# DIAGONAL_POLYPHONIC_SEQUENCER_SIMPLER_VE.net
KiCad netlist of a schematic drawn in EAGLE
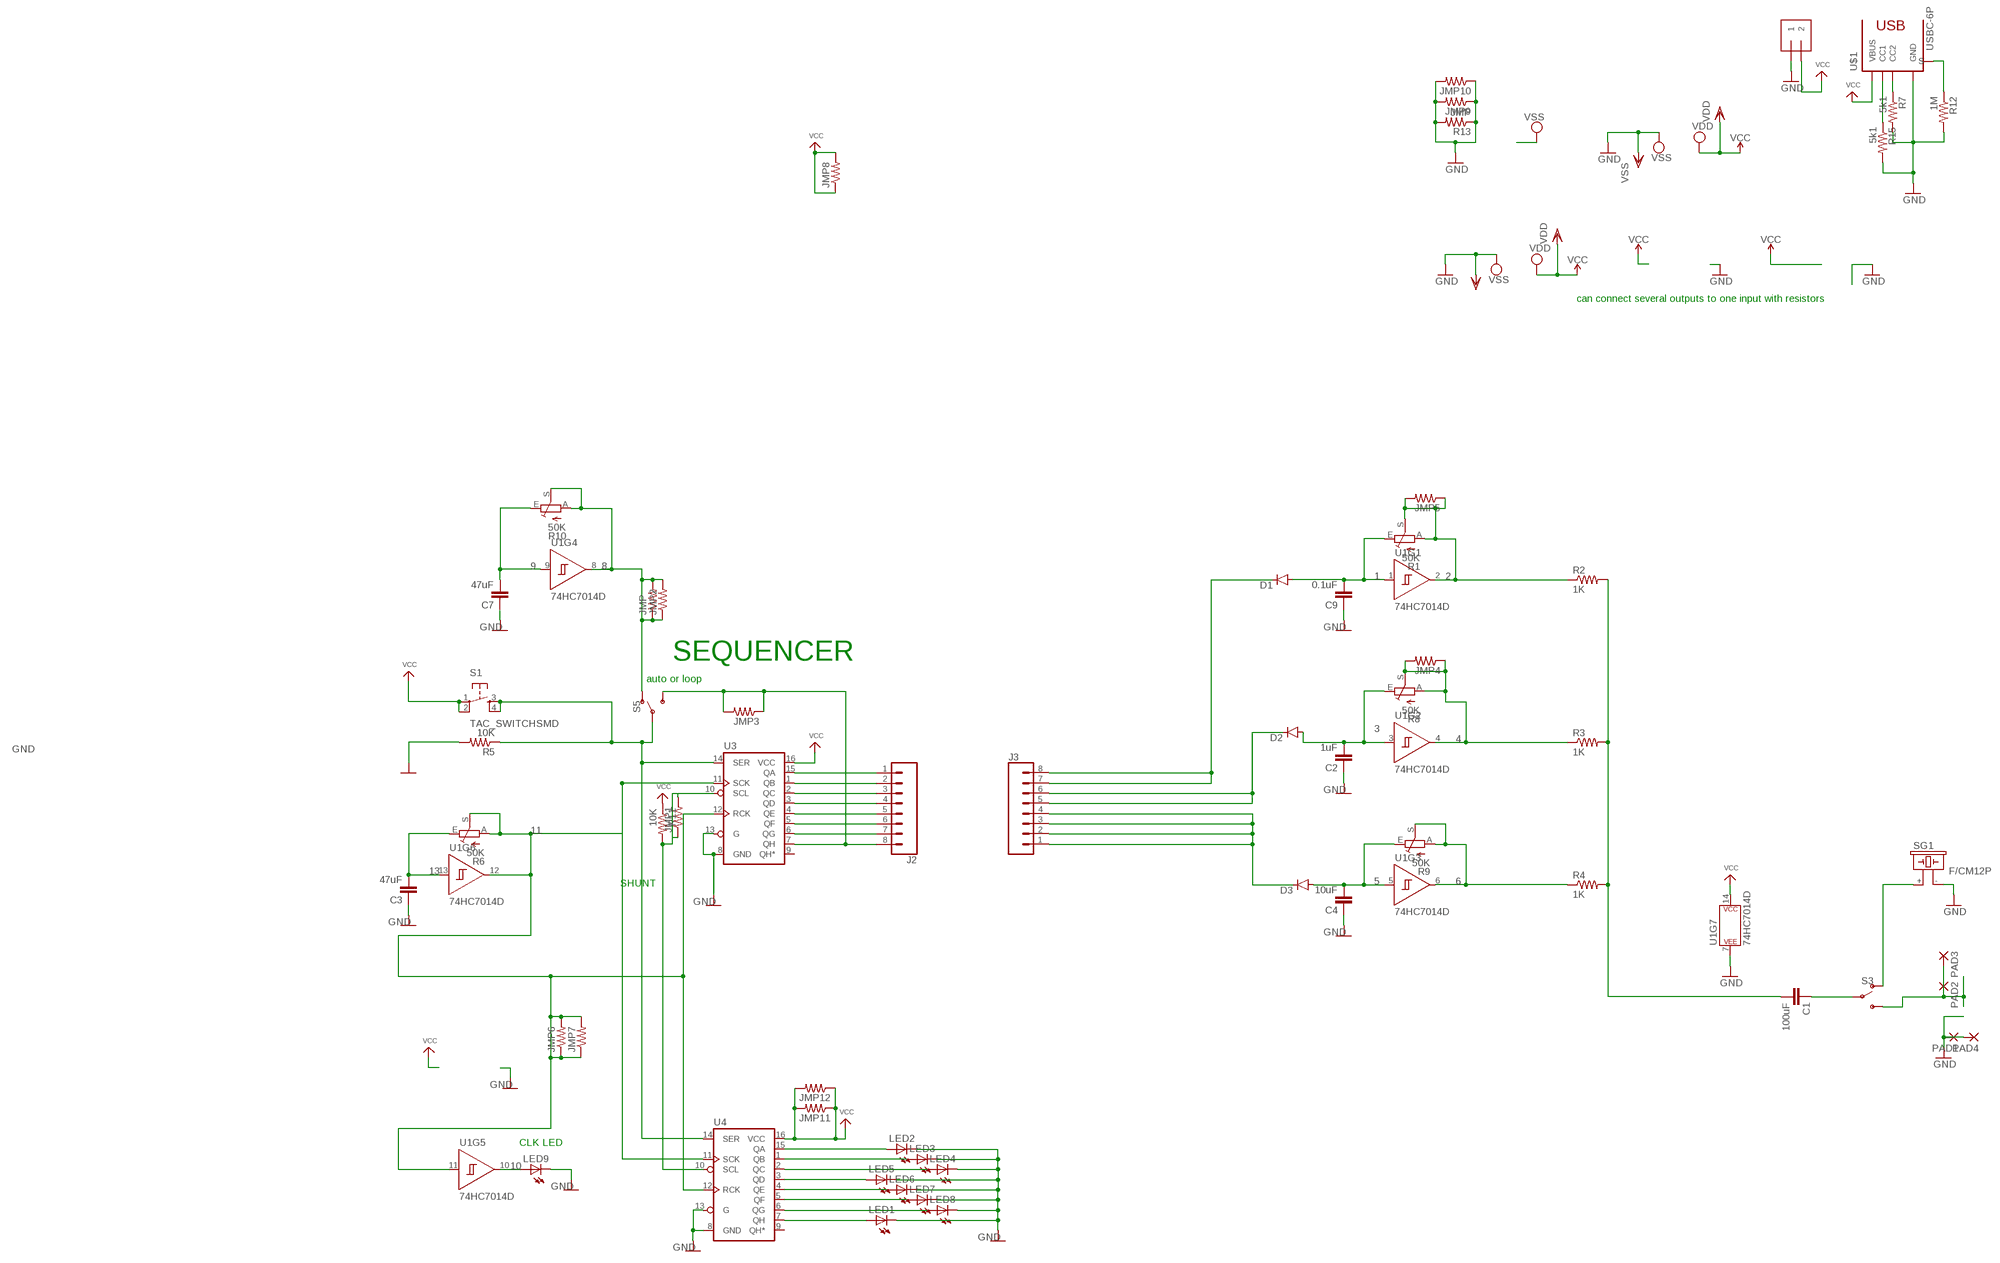
[diagram p0: schematic, sheet 1]

(export (version "E")
  (design (tool "Eeschema 10.0.6"))
  (components
    (comp (ref "C1")
      (value "100uF")
      (footprint "eagle-import:1206")
      (libsource (lib "eagle-import") (part "1.0UF-1206-50V-10%"))
    )
    (comp (ref "C2")
      (value "1uF")
      (footprint "eagle-import:1206")
      (libsource (lib "eagle-import") (part "1.0UF-1206-50V-10%"))
    )
    (comp (ref "C3")
      (value "47uF")
      (footprint "eagle-import:1206")
      (libsource (lib "eagle-import") (part "1.0UF-1206-50V-10%"))
    )
    (comp (ref "C4")
      (value "10uF")
      (footprint "eagle-import:1206")
      (libsource (lib "eagle-import") (part "1.0UF-1206-50V-10%"))
    )
    (comp (ref "C7")
      (value "47uF")
      (footprint "eagle-import:1206")
      (libsource (lib "eagle-import") (part "1.0UF-1206-50V-10%"))
    )
    (comp (ref "C9")
      (value "0.1uF")
      (footprint "eagle-import:1206")
      (libsource (lib "eagle-import") (part "1.0UF-1206-50V-10%"))
    )
    (comp (ref "D1")
      (value "DIODEDO214AA")
      (footprint "eagle-import:DO-214AA")
      (libsource (lib "eagle-import") (part "DIODEDO214AA"))
    )
    (comp (ref "D2")
      (value "DIODEDO214AA")
      (footprint "eagle-import:DO-214AA")
      (libsource (lib "eagle-import") (part "DIODEDO214AA"))
    )
    (comp (ref "D3")
      (value "DIODEDO214AA")
      (footprint "eagle-import:DO-214AA")
      (libsource (lib "eagle-import") (part "DIODEDO214AA"))
    )
    (comp (ref "J1")
      (value "1X2-3.5MM")
      (footprint "eagle-import:1X2-3.5MM")
      (libsource (lib "eagle-import") (part "1X2-3.5MM"))
    )
    (comp (ref "J2")
      (value "CONN_08SMD-STRAIGHT-ALT-FEMALE")
      (footprint "eagle-import:1X08_SMD_ALT")
      (libsource (lib "eagle-import") (part "CONN_08SMD-STRAIGHT-ALT-FEMALE"))
    )
    (comp (ref "J3")
      (value "CONN_08SMD-STRAIGHT-ALT-FEMALE")
      (footprint "eagle-import:1X08_SMD_ALT")
      (libsource (lib "eagle-import") (part "CONN_08SMD-STRAIGHT-ALT-FEMALE"))
    )
    (comp (ref "JMP")
      (value "R-US_R1206")
      (footprint "eagle-import:R1206")
      (libsource (lib "eagle-import") (part "R-US_R1206"))
    )
    (comp (ref "JMP1")
      (value "R-US_R1206")
      (footprint "eagle-import:R1206")
      (libsource (lib "eagle-import") (part "R-US_R1206"))
    )
    (comp (ref "JMP2")
      (value "R-US_R1206")
      (footprint "eagle-import:R1206")
      (libsource (lib "eagle-import") (part "R-US_R1206"))
    )
    (comp (ref "JMP3")
      (value "R-US_R1206")
      (footprint "eagle-import:R1206")
      (libsource (lib "eagle-import") (part "R-US_R1206"))
    )
    (comp (ref "JMP4")
      (value "R-US_R1206")
      (footprint "eagle-import:R1206")
      (libsource (lib "eagle-import") (part "R-US_R1206"))
    )
    (comp (ref "JMP5")
      (value "R-US_R1206")
      (footprint "eagle-import:R1206")
      (libsource (lib "eagle-import") (part "R-US_R1206"))
    )
    (comp (ref "JMP6")
      (value "R-US_R1206")
      (footprint "eagle-import:R1206")
      (libsource (lib "eagle-import") (part "R-US_R1206"))
    )
    (comp (ref "JMP7")
      (value "R-US_R1206")
      (footprint "eagle-import:R1206")
      (libsource (lib "eagle-import") (part "R-US_R1206"))
    )
    (comp (ref "JMP8")
      (value "R-US_R1206")
      (footprint "eagle-import:R1206")
      (libsource (lib "eagle-import") (part "R-US_R1206"))
    )
    (comp (ref "JMP9")
      (value "R-US_R1206")
      (footprint "eagle-import:R1206")
      (libsource (lib "eagle-import") (part "R-US_R1206"))
    )
    (comp (ref "JMP10")
      (value "R-US_R1206")
      (footprint "eagle-import:R1206")
      (libsource (lib "eagle-import") (part "R-US_R1206"))
    )
    (comp (ref "JMP11")
      (value "R-US_R1206")
      (footprint "eagle-import:R1206")
      (libsource (lib "eagle-import") (part "R-US_R1206"))
    )
    (comp (ref "JMP12")
      (value "R-US_R1206")
      (footprint "eagle-import:R1206")
      (libsource (lib "eagle-import") (part "R-US_R1206"))
    )
    (comp (ref "LED1")
      (value "LEDCHIPLED_1206")
      (footprint "eagle-import:CHIPLED_1206")
      (libsource (lib "eagle-import") (part "LEDCHIPLED_1206"))
    )
    (comp (ref "LED2")
      (value "LEDCHIPLED_1206")
      (footprint "eagle-import:CHIPLED_1206")
      (libsource (lib "eagle-import") (part "LEDCHIPLED_1206"))
    )
    (comp (ref "LED3")
      (value "LEDCHIPLED_1206")
      (footprint "eagle-import:CHIPLED_1206")
      (libsource (lib "eagle-import") (part "LEDCHIPLED_1206"))
    )
    (comp (ref "LED4")
      (value "LEDCHIPLED_1206")
      (footprint "eagle-import:CHIPLED_1206")
      (libsource (lib "eagle-import") (part "LEDCHIPLED_1206"))
    )
    (comp (ref "LED5")
      (value "LEDCHIPLED_1206")
      (footprint "eagle-import:CHIPLED_1206")
      (libsource (lib "eagle-import") (part "LEDCHIPLED_1206"))
    )
    (comp (ref "LED6")
      (value "LEDCHIPLED_1206")
      (footprint "eagle-import:CHIPLED_1206")
      (libsource (lib "eagle-import") (part "LEDCHIPLED_1206"))
    )
    (comp (ref "LED7")
      (value "LEDCHIPLED_1206")
      (footprint "eagle-import:CHIPLED_1206")
      (libsource (lib "eagle-import") (part "LEDCHIPLED_1206"))
    )
    (comp (ref "LED8")
      (value "LEDCHIPLED_1206")
      (footprint "eagle-import:CHIPLED_1206")
      (libsource (lib "eagle-import") (part "LEDCHIPLED_1206"))
    )
    (comp (ref "LED9")
      (value "LEDCHIPLED_1206")
      (footprint "eagle-import:CHIPLED_1206")
      (libsource (lib "eagle-import") (part "LEDCHIPLED_1206"))
    )
    (comp (ref "PAD1")
      (value "SMD5")
      (footprint "eagle-import:SMD2,54-5,08")
      (libsource (lib "eagle-import") (part "SMD5"))
    )
    (comp (ref "PAD2")
      (value "SMD5")
      (footprint "eagle-import:SMD2,54-5,08")
      (libsource (lib "eagle-import") (part "SMD5"))
    )
    (comp (ref "PAD3")
      (value "SMD5")
      (footprint "eagle-import:SMD2,54-5,08")
      (libsource (lib "eagle-import") (part "SMD5"))
    )
    (comp (ref "PAD4")
      (value "SMD5")
      (footprint "eagle-import:SMD2,54-5,08")
      (libsource (lib "eagle-import") (part "SMD5"))
    )
    (comp (ref "R1")
      (value "50K")
      (footprint "eagle-import:CA9V")
      (libsource (lib "eagle-import") (part "TRIM_EU-CA9V"))
    )
    (comp (ref "R2")
      (value "1K")
      (footprint "eagle-import:R1206")
      (libsource (lib "eagle-import") (part "R-US_R1206"))
    )
    (comp (ref "R3")
      (value "1K")
      (footprint "eagle-import:R1206")
      (libsource (lib "eagle-import") (part "R-US_R1206"))
    )
    (comp (ref "R4")
      (value "1K")
      (footprint "eagle-import:R1206")
      (libsource (lib "eagle-import") (part "R-US_R1206"))
    )
    (comp (ref "R5")
      (value "10K")
      (footprint "eagle-import:R1206")
      (libsource (lib "eagle-import") (part "R-US_R1206"))
    )
    (comp (ref "R6")
      (value "50K")
      (footprint "eagle-import:CA9V")
      (libsource (lib "eagle-import") (part "TRIM_EU-CA9V"))
    )
    (comp (ref "R7")
      (value "5k1")
      (footprint "eagle-import:R1206")
      (libsource (lib "eagle-import") (part "R-US_R1206"))
    )
    (comp (ref "R8")
      (value "50K")
      (footprint "eagle-import:CA9V")
      (libsource (lib "eagle-import") (part "TRIM_EU-CA9V"))
    )
    (comp (ref "R9")
      (value "50K")
      (footprint "eagle-import:CA9V")
      (libsource (lib "eagle-import") (part "TRIM_EU-CA9V"))
    )
    (comp (ref "R10")
      (value "50K")
      (footprint "eagle-import:CA9V")
      (libsource (lib "eagle-import") (part "TRIM_EU-CA9V"))
    )
    (comp (ref "R11")
      (value "10K")
      (footprint "eagle-import:R1206")
      (libsource (lib "eagle-import") (part "R-US_R1206"))
    )
    (comp (ref "R12")
      (value "1M")
      (footprint "eagle-import:R1206")
      (libsource (lib "eagle-import") (part "R-US_R1206"))
    )
    (comp (ref "R13")
      (value "JMP")
      (footprint "eagle-import:R1206")
      (libsource (lib "eagle-import") (part "R-US_R1206"))
    )
    (comp (ref "R15")
      (value "5k1")
      (footprint "eagle-import:R1206")
      (libsource (lib "eagle-import") (part "R-US_R1206"))
    )
    (comp (ref "S1")
      (value "TAC_SWITCHSMD")
      (footprint "eagle-import:TACTILE-SWITCH-SMD")
      (libsource (lib "eagle-import") (part "TAC_SWITCHSMD"))
    )
    (comp (ref "S3")
      (value "SWITCH-SPDT-SMD-AYZ0202")
      (footprint "eagle-import:SWITCH_DPDT_SMD_AYZ0202")
      (libsource (lib "eagle-import") (part "SWITCH-SPDT-SMD-AYZ0202"))
    )
    (comp (ref "S5")
      (value "SWITCH-SPDT-SMD-AYZ0202")
      (footprint "eagle-import:SWITCH_DPDT_SMD_AYZ0202")
      (libsource (lib "eagle-import") (part "SWITCH-SPDT-SMD-AYZ0202"))
    )
    (comp (ref "SG1")
      (value "F/CM12P")
      (footprint "eagle-import:F_CM12P")
      (libsource (lib "eagle-import") (part "F/CM12P"))
    )
    (comp (ref "U$1")
      (value "USBC-6P")
      (footprint "eagle-import:USCX-06FX-XXMX-01")
      (libsource (lib "eagle-import") (part "USBC-6P"))
    )
    (comp (ref "U1")
      (value "74HC7014D")
      (footprint "eagle-import:SO14")
      (libsource (lib "eagle-import") (part "747014DHC"))
    )
    (comp (ref "U3")
      (value "74595")
      (footprint "eagle-import:TSSOP16")
      (libsource (lib "eagle-import") (part "74595"))
    )
    (comp (ref "U4")
      (value "74595")
      (footprint "eagle-import:TSSOP16")
      (libsource (lib "eagle-import") (part "74595"))
    )
  )
  (nets
    (net (code "1") (name "/1") (class "Default")
      (node (ref "C9") (pin "2") (pinfunction "2_2") (pintype "passive"))
      (node (ref "D1") (pin "A") (pinfunction "A_A") (pintype "passive"))
      (node (ref "R1") (pin "E") (pinfunction "E_E") (pintype "passive"))
      (node (ref "U1") (pin "1") (pinfunction "A_1") (pintype "bidirectional"))
    )
    (net (code "2") (name "/2") (class "Default")
      (node (ref "JMP5") (pin "1") (pinfunction "1_1") (pintype "passive"))
      (node (ref "JMP5") (pin "2") (pinfunction "2_2") (pintype "passive"))
      (node (ref "R1") (pin "A") (pinfunction "A_A") (pintype "passive"))
      (node (ref "R1") (pin "S") (pinfunction "S_S") (pintype "passive"))
      (node (ref "R2") (pin "1") (pinfunction "1_1") (pintype "passive"))
      (node (ref "U1") (pin "2") (pinfunction "Y_2") (pintype "bidirectional"))
    )
    (net (code "3") (name "/3") (class "Default")
      (node (ref "C2") (pin "2") (pinfunction "2_2") (pintype "passive"))
      (node (ref "D2") (pin "A") (pinfunction "A_A") (pintype "passive"))
      (node (ref "R8") (pin "E") (pinfunction "E_E") (pintype "passive"))
      (node (ref "U1") (pin "3") (pinfunction "A_3") (pintype "bidirectional"))
    )
    (net (code "4") (name "/4") (class "Default")
      (node (ref "JMP4") (pin "1") (pinfunction "1_1") (pintype "passive"))
      (node (ref "JMP4") (pin "2") (pinfunction "2_2") (pintype "passive"))
      (node (ref "R3") (pin "1") (pinfunction "1_1") (pintype "passive"))
      (node (ref "R8") (pin "A") (pinfunction "A_A") (pintype "passive"))
      (node (ref "R8") (pin "S") (pinfunction "S_S") (pintype "passive"))
      (node (ref "U1") (pin "4") (pinfunction "Y_4") (pintype "bidirectional"))
    )
    (net (code "5") (name "/5") (class "Default")
      (node (ref "C4") (pin "2") (pinfunction "2_2") (pintype "passive"))
      (node (ref "D3") (pin "A") (pinfunction "A_A") (pintype "passive"))
      (node (ref "R9") (pin "E") (pinfunction "E_E") (pintype "passive"))
      (node (ref "U1") (pin "5") (pinfunction "A_5") (pintype "bidirectional"))
    )
    (net (code "6") (name "/6") (class "Default")
      (node (ref "R4") (pin "1") (pinfunction "1_1") (pintype "passive"))
      (node (ref "R9") (pin "A") (pinfunction "A_A") (pintype "passive"))
      (node (ref "R9") (pin "S") (pinfunction "S_S") (pintype "passive"))
      (node (ref "U1") (pin "6") (pinfunction "Y_6") (pintype "bidirectional"))
    )
    (net (code "7") (name "/8") (class "Default")
      (node (ref "JMP") (pin "1") (pinfunction "1_1") (pintype "passive"))
      (node (ref "JMP") (pin "2") (pinfunction "2_2") (pintype "passive"))
      (node (ref "JMP2") (pin "1") (pinfunction "1_1") (pintype "passive"))
      (node (ref "JMP2") (pin "2") (pinfunction "2_2") (pintype "passive"))
      (node (ref "R10") (pin "A") (pinfunction "A_A") (pintype "passive"))
      (node (ref "R10") (pin "S") (pinfunction "S_S") (pintype "passive"))
      (node (ref "S5") (pin "1") (pinfunction "O_1") (pintype "passive"))
      (node (ref "U1") (pin "8") (pinfunction "Y_8") (pintype "bidirectional"))
    )
    (net (code "8") (name "/9") (class "Default")
      (node (ref "C7") (pin "2") (pinfunction "2_2") (pintype "passive"))
      (node (ref "R10") (pin "E") (pinfunction "E_E") (pintype "passive"))
      (node (ref "U1") (pin "9") (pinfunction "A_9") (pintype "bidirectional"))
    )
    (net (code "9") (name "/10") (class "Default")
      (node (ref "LED9") (pin "A") (pinfunction "A_A") (pintype "passive"))
      (node (ref "U1") (pin "10") (pinfunction "Y_10") (pintype "bidirectional"))
    )
    (net (code "10") (name "/11") (class "Default")
      (node (ref "JMP6") (pin "1") (pinfunction "1_1") (pintype "passive"))
      (node (ref "JMP6") (pin "2") (pinfunction "2_2") (pintype "passive"))
      (node (ref "JMP7") (pin "1") (pinfunction "1_1") (pintype "passive"))
      (node (ref "JMP7") (pin "2") (pinfunction "2_2") (pintype "passive"))
      (node (ref "R6") (pin "A") (pinfunction "A_A") (pintype "passive"))
      (node (ref "R6") (pin "S") (pinfunction "S_S") (pintype "passive"))
      (node (ref "U1") (pin "11") (pinfunction "A_11") (pintype "bidirectional"))
      (node (ref "U1") (pin "12") (pinfunction "Y_12") (pintype "bidirectional"))
      (node (ref "U3") (pin "11") (pinfunction "SCK_11") (pintype "input"))
      (node (ref "U3") (pin "12") (pinfunction "RCK_12") (pintype "input"))
      (node (ref "U4") (pin "11") (pinfunction "SCK_11") (pintype "input"))
      (node (ref "U4") (pin "12") (pinfunction "RCK_12") (pintype "input"))
    )
    (net (code "11") (name "/13") (class "Default")
      (node (ref "C3") (pin "2") (pinfunction "2_2") (pintype "passive"))
      (node (ref "R6") (pin "E") (pinfunction "E_E") (pintype "passive"))
      (node (ref "U1") (pin "13") (pinfunction "A_13") (pintype "bidirectional"))
    )
    (net (code "12") (name "GND") (class "Default")
      (node (ref "C2") (pin "1") (pinfunction "1_1") (pintype "passive"))
      (node (ref "C3") (pin "1") (pinfunction "1_1") (pintype "passive"))
      (node (ref "C4") (pin "1") (pinfunction "1_1") (pintype "passive"))
      (node (ref "C7") (pin "1") (pinfunction "1_1") (pintype "passive"))
      (node (ref "C9") (pin "1") (pinfunction "1_1") (pintype "passive"))
      (node (ref "J1") (pin "1") (pinfunction "1_1") (pintype "passive"))
      (node (ref "JMP10") (pin "1") (pinfunction "1_1") (pintype "passive"))
      (node (ref "JMP10") (pin "2") (pinfunction "2_2") (pintype "passive"))
      (node (ref "JMP9") (pin "1") (pinfunction "1_1") (pintype "passive"))
      (node (ref "JMP9") (pin "2") (pinfunction "2_2") (pintype "passive"))
      (node (ref "LED1") (pin "C") (pinfunction "C_C") (pintype "passive"))
      (node (ref "LED2") (pin "C") (pinfunction "C_C") (pintype "passive"))
      (node (ref "LED3") (pin "C") (pinfunction "C_C") (pintype "passive"))
      (node (ref "LED4") (pin "C") (pinfunction "C_C") (pintype "passive"))
      (node (ref "LED5") (pin "C") (pinfunction "C_C") (pintype "passive"))
      (node (ref "LED6") (pin "C") (pinfunction "C_C") (pintype "passive"))
      (node (ref "LED7") (pin "C") (pinfunction "C_C") (pintype "passive"))
      (node (ref "LED8") (pin "C") (pinfunction "C_C") (pintype "passive"))
      (node (ref "LED9") (pin "C") (pinfunction "C_C") (pintype "passive"))
      (node (ref "PAD1") (pin "1") (pinfunction "P_1") (pintype "passive"))
      (node (ref "PAD4") (pin "1") (pinfunction "P_1") (pintype "passive"))
      (node (ref "R12") (pin "2") (pinfunction "2_2") (pintype "passive"))
      (node (ref "R13") (pin "1") (pinfunction "1_1") (pintype "passive"))
      (node (ref "R13") (pin "2") (pinfunction "2_2") (pintype "passive"))
      (node (ref "R15") (pin "2") (pinfunction "2_2") (pintype "passive"))
      (node (ref "R5") (pin "2") (pinfunction "2_2") (pintype "passive"))
      (node (ref "R7") (pin "2") (pinfunction "2_2") (pintype "passive"))
      (node (ref "SG1") (pin "-") (pinfunction "2_-") (pintype "passive"))
      (node (ref "U$1") (pin "GND1") (pinfunction "GND_GND1") (pintype "power_in"))
      (node (ref "U$1") (pin "GND2") (pinfunction "GND_GND2") (pintype "power_in"))
      (node (ref "U1") (pin "7") (pinfunction "P$V-_7") (pintype "bidirectional"))
      (node (ref "U3") (pin "13") (pinfunction "G_13") (pintype "input"))
      (node (ref "U3") (pin "8") (pinfunction "GND_8") (pintype "power_in"))
      (node (ref "U4") (pin "13") (pinfunction "G_13") (pintype "input"))
      (node (ref "U4") (pin "8") (pinfunction "GND_8") (pintype "power_in"))
    )
    (net (code "13") (name "Net-(C1-Pad2)") (class "Default")
      (node (ref "C1") (pin "2") (pinfunction "2_2") (pintype "passive"))
      (node (ref "R2") (pin "2") (pinfunction "2_2") (pintype "passive"))
      (node (ref "R3") (pin "2") (pinfunction "2_2") (pintype "passive"))
      (node (ref "R4") (pin "2") (pinfunction "2_2") (pintype "passive"))
    )
    (net (code "14") (name "Net-(D1-PadC)") (class "Default")
      (node (ref "D1") (pin "C") (pinfunction "C_C") (pintype "passive"))
      (node (ref "J3") (pin "7") (pinfunction "7_7") (pintype "passive"))
      (node (ref "J3") (pin "8") (pinfunction "8_8") (pintype "passive"))
    )
    (net (code "15") (name "Net-(D2-PadC)") (class "Default")
      (node (ref "D2") (pin "C") (pinfunction "C_C") (pintype "passive"))
      (node (ref "J3") (pin "5") (pinfunction "5_5") (pintype "passive"))
      (node (ref "J3") (pin "6") (pinfunction "6_6") (pintype "passive"))
    )
    (net (code "16") (name "Net-(D3-PadC)") (class "Default")
      (node (ref "D3") (pin "C") (pinfunction "C_C") (pintype "passive"))
      (node (ref "J3") (pin "1") (pinfunction "1_1") (pintype "passive"))
      (node (ref "J3") (pin "2") (pinfunction "2_2") (pintype "passive"))
      (node (ref "J3") (pin "3") (pinfunction "3_3") (pintype "passive"))
      (node (ref "J3") (pin "4") (pinfunction "4_4") (pintype "passive"))
    )
    (net (code "17") (name "Net-(PAD2-P)") (class "Default")
      (node (ref "PAD2") (pin "1") (pinfunction "P_1") (pintype "passive"))
      (node (ref "PAD3") (pin "1") (pinfunction "P_1") (pintype "passive"))
      (node (ref "S3") (pin "3") (pinfunction "S_3") (pintype "passive"))
    )
    (net (code "18") (name "Net-(R7-Pad1)") (class "Default")
      (node (ref "R7") (pin "1") (pinfunction "1_1") (pintype "passive"))
      (node (ref "U$1") (pin "CC2") (pinfunction "CC2_CC2") (pintype "bidirectional"))
    )
    (net (code "19") (name "Net-(R12-Pad1)") (class "Default")
      (node (ref "R12") (pin "1") (pinfunction "1_1") (pintype "passive"))
      (node (ref "U$1") (pin "SHIELD1") (pinfunction "S_SHIELD1") (pintype "passive"))
      (node (ref "U$1") (pin "SHIELD2") (pinfunction "S_SHIELD2") (pintype "passive"))
      (node (ref "U$1") (pin "SHIELD3") (pinfunction "S_SHIELD3") (pintype "passive"))
      (node (ref "U$1") (pin "SHIELD4") (pinfunction "S_SHIELD4") (pintype "passive"))
    )
    (net (code "20") (name "Net-(R15-Pad1)") (class "Default")
      (node (ref "R15") (pin "1") (pinfunction "1_1") (pintype "passive"))
      (node (ref "U$1") (pin "CC1") (pinfunction "CC1_CC1") (pintype "bidirectional"))
    )
    (net (code "21") (name "Net-(S3-O)") (class "Default")
      (node (ref "S3") (pin "1") (pinfunction "O_1") (pintype "passive"))
      (node (ref "SG1") (pin "+") (pinfunction "1_+") (pintype "passive"))
    )
    (net (code "22") (name "Net-(S3-P)") (class "Default")
      (node (ref "C1") (pin "1") (pinfunction "1_1") (pintype "passive"))
      (node (ref "S3") (pin "2") (pinfunction "P_2") (pintype "passive"))
    )
    (net (code "23") (name "Net-(S5-P)") (class "Default")
      (node (ref "R5") (pin "1") (pinfunction "1_1") (pintype "passive"))
      (node (ref "S1") (pin "3") (pinfunction "3_3") (pintype "passive"))
      (node (ref "S1") (pin "4") (pinfunction "4_4") (pintype "passive"))
      (node (ref "S5") (pin "2") (pinfunction "P_2") (pintype "passive"))
      (node (ref "U3") (pin "14") (pinfunction "SER_14") (pintype "input"))
      (node (ref "U4") (pin "14") (pinfunction "SER_14") (pintype "input"))
    )
    (net (code "24") (name "Net-(S5-S)") (class "Default")
      (node (ref "J2") (pin "8") (pinfunction "8_8") (pintype "passive"))
      (node (ref "JMP3") (pin "1") (pinfunction "1_1") (pintype "passive"))
      (node (ref "JMP3") (pin "2") (pinfunction "2_2") (pintype "passive"))
      (node (ref "S5") (pin "3") (pinfunction "S_3") (pintype "passive"))
      (node (ref "U3") (pin "7") (pinfunction "QH_7") (pintype "tri_state"))
    )
    (net (code "25") (name "Net-(U3-QA)") (class "Default")
      (node (ref "J2") (pin "1") (pinfunction "1_1") (pintype "passive"))
      (node (ref "U3") (pin "15") (pinfunction "QA_15") (pintype "tri_state"))
    )
    (net (code "26") (name "Net-(U3-QB)") (class "Default")
      (node (ref "J2") (pin "2") (pinfunction "2_2") (pintype "passive"))
      (node (ref "U3") (pin "1") (pinfunction "QB_1") (pintype "tri_state"))
    )
    (net (code "27") (name "Net-(U3-QC)") (class "Default")
      (node (ref "J2") (pin "3") (pinfunction "3_3") (pintype "passive"))
      (node (ref "U3") (pin "2") (pinfunction "QC_2") (pintype "tri_state"))
    )
    (net (code "28") (name "Net-(U3-QD)") (class "Default")
      (node (ref "J2") (pin "4") (pinfunction "4_4") (pintype "passive"))
      (node (ref "U3") (pin "3") (pinfunction "QD_3") (pintype "tri_state"))
    )
    (net (code "29") (name "Net-(U3-QE)") (class "Default")
      (node (ref "J2") (pin "5") (pinfunction "5_5") (pintype "passive"))
      (node (ref "U3") (pin "4") (pinfunction "QE_4") (pintype "tri_state"))
    )
    (net (code "30") (name "Net-(U3-QF)") (class "Default")
      (node (ref "J2") (pin "6") (pinfunction "6_6") (pintype "passive"))
      (node (ref "U3") (pin "5") (pinfunction "QF_5") (pintype "tri_state"))
    )
    (net (code "31") (name "Net-(U3-QG)") (class "Default")
      (node (ref "J2") (pin "7") (pinfunction "7_7") (pintype "passive"))
      (node (ref "U3") (pin "6") (pinfunction "QG_6") (pintype "tri_state"))
    )
    (net (code "32") (name "Net-(U3-SCL)") (class "Default")
      (node (ref "JMP1") (pin "1") (pinfunction "1_1") (pintype "passive"))
      (node (ref "JMP1") (pin "2") (pinfunction "2_2") (pintype "passive"))
      (node (ref "R11") (pin "2") (pinfunction "2_2") (pintype "passive"))
      (node (ref "U3") (pin "10") (pinfunction "SCL_10") (pintype "input"))
      (node (ref "U4") (pin "10") (pinfunction "SCL_10") (pintype "input"))
    )
    (net (code "33") (name "Net-(U4-QA)") (class "Default")
      (node (ref "LED2") (pin "A") (pinfunction "A_A") (pintype "passive"))
      (node (ref "U4") (pin "15") (pinfunction "QA_15") (pintype "tri_state"))
    )
    (net (code "34") (name "Net-(U4-QB)") (class "Default")
      (node (ref "LED3") (pin "A") (pinfunction "A_A") (pintype "passive"))
      (node (ref "U4") (pin "1") (pinfunction "QB_1") (pintype "tri_state"))
    )
    (net (code "35") (name "Net-(U4-QC)") (class "Default")
      (node (ref "LED4") (pin "A") (pinfunction "A_A") (pintype "passive"))
      (node (ref "U4") (pin "2") (pinfunction "QC_2") (pintype "tri_state"))
    )
    (net (code "36") (name "Net-(U4-QD)") (class "Default")
      (node (ref "LED5") (pin "A") (pinfunction "A_A") (pintype "passive"))
      (node (ref "U4") (pin "3") (pinfunction "QD_3") (pintype "tri_state"))
    )
    (net (code "37") (name "Net-(U4-QE)") (class "Default")
      (node (ref "LED6") (pin "A") (pinfunction "A_A") (pintype "passive"))
      (node (ref "U4") (pin "4") (pinfunction "QE_4") (pintype "tri_state"))
    )
    (net (code "38") (name "Net-(U4-QF)") (class "Default")
      (node (ref "LED7") (pin "A") (pinfunction "A_A") (pintype "passive"))
      (node (ref "U4") (pin "5") (pinfunction "QF_5") (pintype "tri_state"))
    )
    (net (code "39") (name "Net-(U4-QG)") (class "Default")
      (node (ref "LED8") (pin "A") (pinfunction "A_A") (pintype "passive"))
      (node (ref "U4") (pin "6") (pinfunction "QG_6") (pintype "tri_state"))
    )
    (net (code "40") (name "Net-(U4-QH)") (class "Default")
      (node (ref "LED1") (pin "A") (pinfunction "A_A") (pintype "passive"))
      (node (ref "U4") (pin "7") (pinfunction "QH_7") (pintype "tri_state"))
    )
    (net (code "41") (name "VCC") (class "Default")
      (node (ref "J1") (pin "2") (pinfunction "2_2") (pintype "passive"))
      (node (ref "JMP11") (pin "1") (pinfunction "1_1") (pintype "passive"))
      (node (ref "JMP11") (pin "2") (pinfunction "2_2") (pintype "passive"))
      (node (ref "JMP12") (pin "1") (pinfunction "1_1") (pintype "passive"))
      (node (ref "JMP12") (pin "2") (pinfunction "2_2") (pintype "passive"))
      (node (ref "JMP8") (pin "1") (pinfunction "1_1") (pintype "passive"))
      (node (ref "JMP8") (pin "2") (pinfunction "2_2") (pintype "passive"))
      (node (ref "R11") (pin "1") (pinfunction "1_1") (pintype "passive"))
      (node (ref "S1") (pin "1") (pinfunction "1_1") (pintype "passive"))
      (node (ref "S1") (pin "2") (pinfunction "2_2") (pintype "passive"))
      (node (ref "U$1") (pin "VBUS1") (pinfunction "VBUS_VBUS1") (pintype "power_in"))
      (node (ref "U$1") (pin "VBUS2") (pinfunction "VBUS_VBUS2") (pintype "power_in"))
      (node (ref "U1") (pin "14") (pinfunction "P$V+_14") (pintype "bidirectional"))
      (node (ref "U3") (pin "16") (pinfunction "VCC_16") (pintype "power_in"))
      (node (ref "U4") (pin "16") (pinfunction "VCC_16") (pintype "power_in"))
    )
    (net (code "42") (name "unconnected-(U3-QH*-Pad9)") (class "Default")
      (node (ref "U3") (pin "9") (pinfunction "QH*_9") (pintype "tri_state"))
    )
    (net (code "43") (name "unconnected-(U4-QH*-Pad9)") (class "Default")
      (node (ref "U4") (pin "9") (pinfunction "QH*_9") (pintype "tri_state"))
    )
  )
)
